# Simple_Sensor_Board.net
KiCad netlist of a schematic drawn in Altium Designer
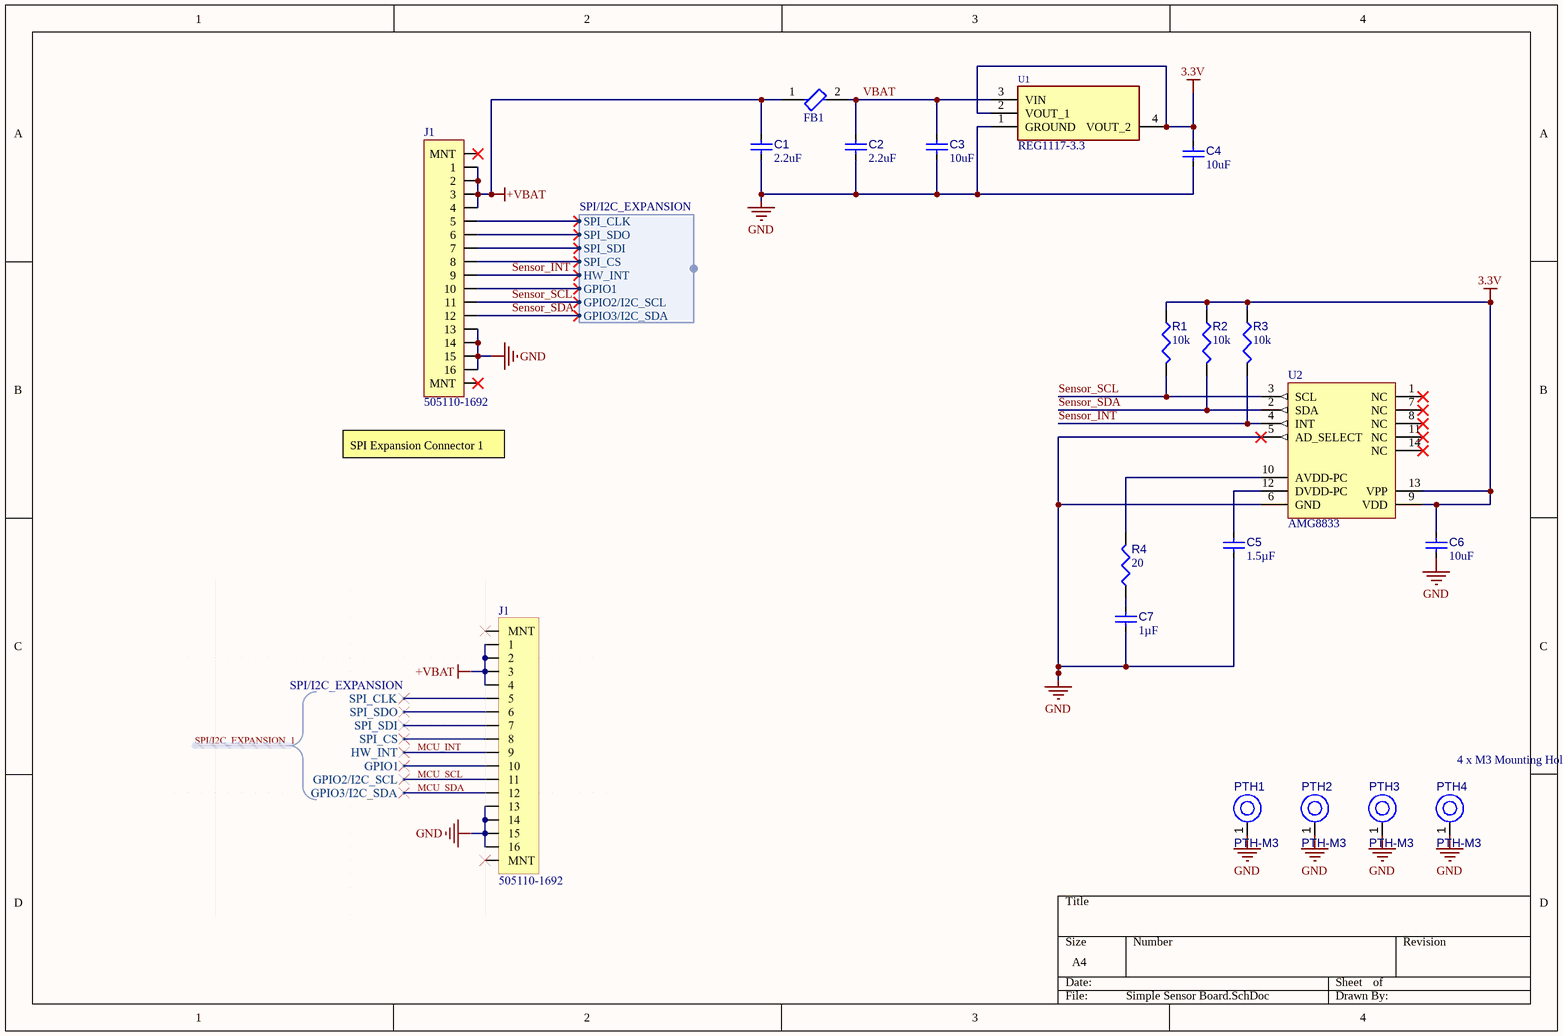
[diagram p0: Simple Sensor Board.SchDoc]

(export (version "E")
  (design (tool "Eeschema 10.0.6"))
  (components
    (comp (ref "C1")
      (value "2.2uF")
      (footprint "CAPC2013X95X50ML10T25")
      (description "Chip Capacitor, 2.2 uF, +/- 10%, 16 V, 0805 (2012 Metric)")
      (fields (field (name "TOLERANCE") "10%") (field (name "Comment") "Capacitor 2.2 uF +/-10% 16 V 0805"))
      (libsource (lib "AERO3001 Spacecraft Project") (part "CAP-NP-2"))
    )
    (comp (ref "C2")
      (value "2.2uF")
      (footprint "CAPC2013X95X50ML10T25")
      (description "Chip Capacitor, 2.2 uF, +/- 10%, 16 V, 0805 (2012 Metric)")
      (fields (field (name "TOLERANCE") "10%") (field (name "Comment") "Capacitor 2.2 uF +/-10% 16 V 0805"))
      (libsource (lib "AERO3001 Spacecraft Project") (part "CAP-NP-2"))
    )
    (comp (ref "C3")
      (value "10uF")
      (footprint "CAPC3216X180X50ML20T25")
      (description "Chip Capacitor, 10 uF, +/- 10%, 10 V, 1206 (3216 Metric)")
      (fields (field (name "TOLERANCE") "10%") (field (name "Comment") "Capacitor 10 uF +/- 10% 10 V 1206"))
      (libsource (lib "AERO3001 Spacecraft Project") (part "CAP-NP-2"))
    )
    (comp (ref "C4")
      (value "10uF")
      (footprint "CAPC3216X180X50ML20T25")
      (description "Chip Capacitor, 10 uF, +/- 10%, 10 V, 1206 (3216 Metric)")
      (fields (field (name "TOLERANCE") "10%") (field (name "Comment") "Capacitor 10 uF +/- 10% 10 V 1206"))
      (libsource (lib "AERO3001 Spacecraft Project") (part "CAP-NP-2"))
    )
    (comp (ref "C5")
      (value "1.5µF")
      (footprint "CAPC1608X90X40ML10T20")
      (description "Chip Capacitor, 1.5 uF, +/-10%, 25 V, 0603(1608 Metric)")
      (fields (field (name "TOLERANCE") "10%") (field (name "Comment") "Capacitor 1.5 uF +/- 10% 25 V 0603"))
      (libsource (lib "AERO3001 Spacecraft Project") (part "CAP-NP-2"))
    )
    (comp (ref "C6")
      (value "10uF")
      (footprint "CAPC3216X180X50ML20T25")
      (description "Chip Capacitor, 10 uF, +/- 10%, 10 V, 1206 (3216 Metric)")
      (fields (field (name "TOLERANCE") "10%") (field (name "Comment") "Capacitor 10 uF +/- 10% 10 V 1206"))
      (libsource (lib "AERO3001 Spacecraft Project") (part "CAP-NP-2"))
    )
    (comp (ref "C7")
      (value "1µF")
      (footprint "CAPC1608X90X40ML10T20")
      (description "Chip Capacitor, 1 uF, +/-10%, 25 V, 0603(1608 Metric)")
      (fields (field (name "TOLERANCE") "10%") (field (name "Comment") "Capacitor 1 uF +/- 10% 25 V 0603"))
      (libsource (lib "AERO3001 Spacecraft Project") (part "CAP-NP-2"))
    )
    (comp (ref "FB1")
      (value "BLM15AX601SZ1D")
      (footprint "FP-BLM15-0_05-IPC_A")
      (description "Ferrite Beads Multi-Layer 600Ohm 25% 100MHz 0.5A 0.34Ohm DCR 0402 Automotive T/R")
      (libsource (lib "AERO3001 Spacecraft Project") (part "5f30dd21d616792df468990f7003faa"))
    )
    (comp (ref "J1")
      (value "505110-1692")
      (footprint "FP-505110-1692-MFG")
      (description "Conn FFC/FPC Connector SKT 16 POS 0.5mm Solder RA SMD Easy-On™ T/R")
      (libsource (lib "AERO3001 Spacecraft Project") (part "505110-1692"))
    )
    (comp (ref "PTH1")
      (value "PTH-M3")
      (footprint "PTH-M3")
      (description "M3 Plated Through Hole, 8mm Diameter Pad")
      (libsource (lib "AERO3001 Spacecraft Project") (part "CMP-00028-00000-1"))
    )
    (comp (ref "PTH2")
      (value "PTH-M3")
      (footprint "PTH-M3")
      (description "M3 Plated Through Hole, 8mm Diameter Pad")
      (libsource (lib "AERO3001 Spacecraft Project") (part "CMP-00028-00000-1"))
    )
    (comp (ref "PTH3")
      (value "PTH-M3")
      (footprint "PTH-M3")
      (description "M3 Plated Through Hole, 8mm Diameter Pad")
      (libsource (lib "AERO3001 Spacecraft Project") (part "CMP-00028-00000-1"))
    )
    (comp (ref "PTH4")
      (value "PTH-M3")
      (footprint "PTH-M3")
      (description "M3 Plated Through Hole, 8mm Diameter Pad")
      (libsource (lib "AERO3001 Spacecraft Project") (part "CMP-00028-00000-1"))
    )
    (comp (ref "R1")
      (value "10k")
      (footprint "RESC1608X55X25ML10T15")
      (description "Chip Resistor, 10 KOhm, +/- 1%, 01 W, -55 to 155 degC, 0603 (1608 Metric)")
      (fields (field (name "POWER") "100mW") (field (name "TOLERANCE") "1%"))
      (libsource (lib "AERO3001 Spacecraft Project") (part "RES-2"))
    )
    (comp (ref "R2")
      (value "10k")
      (footprint "RESC1608X55X25ML10T15")
      (description "Chip Resistor, 10 KOhm, +/- 1%, 01 W, -55 to 155 degC, 0603 (1608 Metric)")
      (fields (field (name "POWER") "100mW") (field (name "TOLERANCE") "1%"))
      (libsource (lib "AERO3001 Spacecraft Project") (part "RES-2"))
    )
    (comp (ref "R3")
      (value "10k")
      (footprint "RESC1608X55X25ML10T15")
      (description "Chip Resistor, 10 KOhm, +/- 1%, 01 W, -55 to 155 degC, 0603 (1608 Metric)")
      (fields (field (name "POWER") "100mW") (field (name "TOLERANCE") "1%"))
      (libsource (lib "AERO3001 Spacecraft Project") (part "RES-2"))
    )
    (comp (ref "R4")
      (value "20")
      (footprint "RESC1608X55X25ML10T15")
      (description "Chip Resistor, 20 Ohm, +/- 1%, 0.1 W, -55 to 155 degC, 0603 (1608 Metric)")
      (fields (field (name "TOLERANCE") "1%") (field (name "POWER") "100mW"))
      (libsource (lib "AERO3001 Spacecraft Project") (part "RES-2"))
    )
    (comp (ref "U1")
      (value "REG1117-3.3")
      (footprint "SamacSys:SOT230P700X180-4N")
      (description "Integrated Circuit")
      (fields (field (name "MOUSER2 PART NUMBER") "595-REG1117-3.3"))
      (libsource (lib "*") (part "REG1117-3.3"))
    )
    (comp (ref "U2")
      (value "AMG8833")
      (footprint "PNSC-AMG8833_V")
      (description "Infrared Array Sensor, Grid-EYE, 8 Pixels H, 8 Pixels V, 3.3V, High Gain Type")
      (libsource (lib "AERO3001 Spacecraft Project") (part "PNSC-AMG8833-14"))
    )
  )
  (nets
    (net (code "1") (name "+VBAT") (class "Default")
      (node (ref "C1") (pin "2") (pinfunction "2_2") (pintype "passive"))
      (node (ref "FB1") (pin "1") (pinfunction "1_1") (pintype "passive"))
      (node (ref "J1") (pin "1") (pinfunction "1_1") (pintype "passive"))
      (node (ref "J1") (pin "2") (pinfunction "2_2") (pintype "passive"))
      (node (ref "J1") (pin "3") (pinfunction "3_3") (pintype "passive"))
      (node (ref "J1") (pin "4") (pinfunction "4_4") (pintype "passive"))
    )
    (net (code "2") (name "/GPIO1") (class "Default")
      (node (ref "J1") (pin "10") (pinfunction "10_10") (pintype "passive+no_connect"))
    )
    (net (code "3") (name "/SPI_CLK") (class "Default")
      (node (ref "J1") (pin "5") (pinfunction "5_5") (pintype "passive+no_connect"))
    )
    (net (code "4") (name "/SPI_CS") (class "Default")
      (node (ref "J1") (pin "8") (pinfunction "8_8") (pintype "passive+no_connect"))
    )
    (net (code "5") (name "/SPI_SDI") (class "Default")
      (node (ref "J1") (pin "7") (pinfunction "7_7") (pintype "passive+no_connect"))
    )
    (net (code "6") (name "/SPI_SDO") (class "Default")
      (node (ref "J1") (pin "6") (pinfunction "6_6") (pintype "passive+no_connect"))
    )
    (net (code "7") (name "/Sensor_INT") (class "Default")
      (node (ref "J1") (pin "9") (pinfunction "9_9") (pintype "passive"))
      (node (ref "R3") (pin "2") (pinfunction "2_2") (pintype "passive"))
      (node (ref "U2") (pin "4") (pinfunction "INT_4") (pintype "output"))
    )
    (net (code "8") (name "/Sensor_SCL") (class "Default")
      (node (ref "J1") (pin "11") (pinfunction "11_11") (pintype "passive"))
      (node (ref "R1") (pin "2") (pinfunction "2_2") (pintype "passive"))
      (node (ref "U2") (pin "3") (pinfunction "SCL_3") (pintype "output"))
    )
    (net (code "9") (name "/Sensor_SDA") (class "Default")
      (node (ref "J1") (pin "12") (pinfunction "12_12") (pintype "passive"))
      (node (ref "R2") (pin "2") (pinfunction "2_2") (pintype "passive"))
      (node (ref "U2") (pin "2") (pinfunction "SDA_2") (pintype "output"))
    )
    (net (code "10") (name "/VBAT") (class "Default")
      (node (ref "C2") (pin "2") (pinfunction "2_2") (pintype "passive"))
      (node (ref "C3") (pin "2") (pinfunction "2_2") (pintype "passive"))
      (node (ref "FB1") (pin "2") (pinfunction "2_2") (pintype "passive"))
      (node (ref "U1") (pin "3") (pinfunction "VIN_3") (pintype "passive"))
    )
    (net (code "11") (name "3.3V") (class "Default")
      (node (ref "C4") (pin "2") (pinfunction "2_2") (pintype "passive"))
      (node (ref "C6") (pin "2") (pinfunction "2_2") (pintype "passive"))
      (node (ref "R1") (pin "1") (pinfunction "1_1") (pintype "passive"))
      (node (ref "R2") (pin "1") (pinfunction "1_1") (pintype "passive"))
      (node (ref "R3") (pin "1") (pinfunction "1_1") (pintype "passive"))
      (node (ref "U1") (pin "2") (pinfunction "VOUT_1_2") (pintype "passive"))
      (node (ref "U1") (pin "4") (pinfunction "VOUT_2_4") (pintype "passive"))
      (node (ref "U2") (pin "13") (pinfunction "VPP_13") (pintype "power_in"))
      (node (ref "U2") (pin "9") (pinfunction "VDD_9") (pintype "power_in"))
    )
    (net (code "12") (name "GND") (class "Default")
      (node (ref "C1") (pin "1") (pinfunction "1_1") (pintype "passive"))
      (node (ref "C2") (pin "1") (pinfunction "1_1") (pintype "passive"))
      (node (ref "C3") (pin "1") (pinfunction "1_1") (pintype "passive"))
      (node (ref "C4") (pin "1") (pinfunction "1_1") (pintype "passive"))
      (node (ref "C5") (pin "1") (pinfunction "1_1") (pintype "passive"))
      (node (ref "C6") (pin "1") (pinfunction "1_1") (pintype "passive"))
      (node (ref "C7") (pin "1") (pinfunction "1_1") (pintype "passive"))
      (node (ref "J1") (pin "13") (pinfunction "13_13") (pintype "passive"))
      (node (ref "J1") (pin "14") (pinfunction "14_14") (pintype "passive"))
      (node (ref "J1") (pin "15") (pinfunction "15_15") (pintype "passive"))
      (node (ref "J1") (pin "16") (pinfunction "16_16") (pintype "passive"))
      (node (ref "PTH1") (pin "1") (pinfunction "H1_1") (pintype "passive"))
      (node (ref "PTH2") (pin "1") (pinfunction "H1_1") (pintype "passive"))
      (node (ref "PTH3") (pin "1") (pinfunction "H1_1") (pintype "passive"))
      (node (ref "PTH4") (pin "1") (pinfunction "H1_1") (pintype "passive"))
      (node (ref "U1") (pin "1") (pinfunction "GROUND_1") (pintype "passive"))
      (node (ref "U2") (pin "5") (pinfunction "AD_SELECT_5") (pintype "output"))
      (node (ref "U2") (pin "6") (pinfunction "GND_6") (pintype "power_in"))
    )
    (net (code "13") (name "Net-(C7-Pad2)") (class "Default")
      (node (ref "C7") (pin "2") (pinfunction "2_2") (pintype "passive"))
      (node (ref "R4") (pin "1") (pinfunction "1_1") (pintype "passive"))
    )
    (net (code "14") (name "Net-(U2-AVDD-PC)") (class "Default")
      (node (ref "R4") (pin "2") (pinfunction "2_2") (pintype "passive"))
      (node (ref "U2") (pin "10") (pinfunction "AVDD-PC_10") (pintype "power_in"))
    )
    (net (code "15") (name "Net-(U2-DVDD-PC)") (class "Default")
      (node (ref "C5") (pin "2") (pinfunction "2_2") (pintype "passive"))
      (node (ref "U2") (pin "12") (pinfunction "DVDD-PC_12") (pintype "power_in"))
    )
    (net (code "16") (name "unconnected-(J1-MNT-Pad17)") (class "Default")
      (node (ref "J1") (pin "17") (pinfunction "MNT_17") (pintype "passive+no_connect"))
    )
    (net (code "17") (name "unconnected-(J1-MNT-Pad18)") (class "Default")
      (node (ref "J1") (pin "18") (pinfunction "MNT_18") (pintype "passive+no_connect"))
    )
    (net (code "18") (name "unconnected-(U2-NC-Pad1)") (class "Default")
      (node (ref "U2") (pin "1") (pinfunction "NC_1") (pintype "passive+no_connect"))
    )
    (net (code "19") (name "unconnected-(U2-NC-Pad7)") (class "Default")
      (node (ref "U2") (pin "7") (pinfunction "NC_7") (pintype "passive+no_connect"))
    )
    (net (code "20") (name "unconnected-(U2-NC-Pad8)") (class "Default")
      (node (ref "U2") (pin "8") (pinfunction "NC_8") (pintype "passive+no_connect"))
    )
    (net (code "21") (name "unconnected-(U2-NC-Pad11)") (class "Default")
      (node (ref "U2") (pin "11") (pinfunction "NC_11") (pintype "passive+no_connect"))
    )
    (net (code "22") (name "unconnected-(U2-NC-Pad14)") (class "Default")
      (node (ref "U2") (pin "14") (pinfunction "NC_14") (pintype "passive+no_connect"))
    )
  )
)
